# untitled.net
KiCad netlist of a schematic drawn in EAGLE
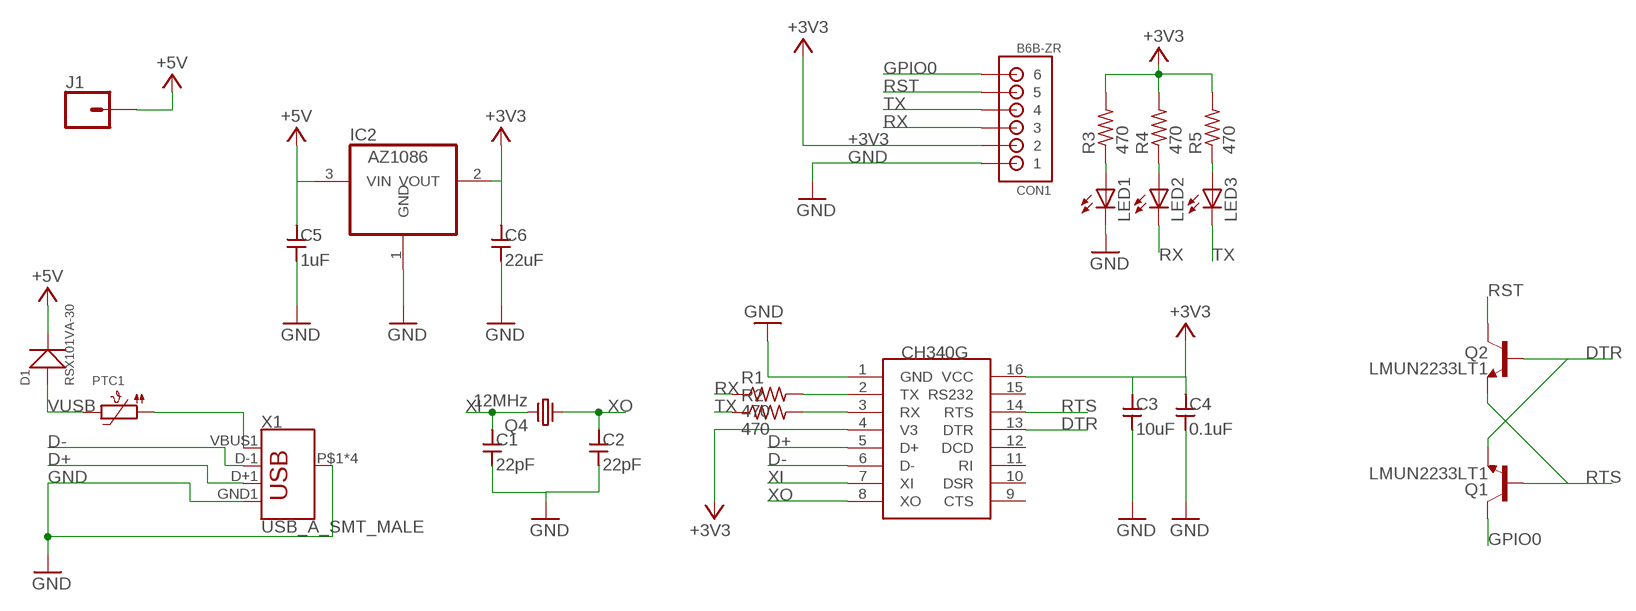
[diagram p0: schematic, sheet 1]

(export (version "E")
  (design (tool "Eeschema 10.0.6"))
  (components
    (comp (ref "C1")
      (value "22pF")
      (footprint "eagle-import:SMD1608")
      (libsource (lib "eagle-import") (part "CAPACITOR1608"))
    )
    (comp (ref "C2")
      (value "22pF")
      (footprint "eagle-import:SMD1608")
      (libsource (lib "eagle-import") (part "CAPACITOR1608"))
    )
    (comp (ref "C3")
      (value "10uF")
      (footprint "eagle-import:SMD1608")
      (libsource (lib "eagle-import") (part "CAPACITOR1608"))
    )
    (comp (ref "C4")
      (value "0.1uF")
      (footprint "eagle-import:SMD1608")
      (libsource (lib "eagle-import") (part "CAPACITOR1608"))
    )
    (comp (ref "C5")
      (value "1uF")
      (footprint "eagle-import:SMD1608")
      (libsource (lib "eagle-import") (part "CAPACITOR1608"))
    )
    (comp (ref "C6")
      (value "22uF")
      (footprint "eagle-import:SMD1608")
      (libsource (lib "eagle-import") (part "CAPACITOR1608"))
    )
    (comp (ref "CON1")
      (value "B6B-ZR")
      (footprint "eagle-import:B6B-ZR")
      (libsource (lib "eagle-import") (part "B6B-ZR"))
    )
    (comp (ref "D1")
      (value "RSX101VA-30")
      (footprint "eagle-import:TUMD2")
      (libsource (lib "eagle-import") (part "DIODETUMD2"))
    )
    (comp (ref "IC2")
      (value "AZ1086")
      (footprint "eagle-import:SOT223")
      (libsource (lib "eagle-import") (part "AZ1086"))
    )
    (comp (ref "J1")
      (value "CONN_01PTH_NO_SILK_YES_STOP")
      (footprint "eagle-import:1X01_NO_SILK")
      (libsource (lib "eagle-import") (part "CONN_01PTH_NO_SILK_YES_STOP"))
    )
    (comp (ref "LED1")
      (value "LEDCHIPLED_0603")
      (footprint "eagle-import:CHIPLED_0603")
      (libsource (lib "eagle-import") (part "LEDCHIPLED_0603"))
    )
    (comp (ref "LED2")
      (value "LEDCHIPLED_0603")
      (footprint "eagle-import:CHIPLED_0603")
      (libsource (lib "eagle-import") (part "LEDCHIPLED_0603"))
    )
    (comp (ref "LED3")
      (value "LEDCHIPLED_0603")
      (footprint "eagle-import:CHIPLED_0603")
      (libsource (lib "eagle-import") (part "LEDCHIPLED_0603"))
    )
    (comp (ref "PTC1")
      (value "PTC0805")
      (footprint "eagle-import:0805")
      (libsource (lib "eagle-import") (part "PTC0805"))
    )
    (comp (ref "Q1")
      (value "LMUN2233LT1")
      (footprint "eagle-import:SOT23-3")
      (libsource (lib "eagle-import") (part "LMUN2233LT1"))
    )
    (comp (ref "Q2")
      (value "LMUN2233LT1")
      (footprint "eagle-import:SOT23-3")
      (libsource (lib "eagle-import") (part "LMUN2233LT1"))
    )
    (comp (ref "Q4")
      (value "12MHz")
      (footprint "eagle-import:TC26H")
      (libsource (lib "eagle-import") (part "CRYSTAL-TC26H"))
    )
    (comp (ref "R1")
      (value "470")
      (footprint "eagle-import:R0603")
      (libsource (lib "eagle-import") (part "R-US_R0603"))
    )
    (comp (ref "R2")
      (value "470")
      (footprint "eagle-import:R0603")
      (libsource (lib "eagle-import") (part "R-US_R0603"))
    )
    (comp (ref "R3")
      (value "470")
      (footprint "eagle-import:R0603")
      (libsource (lib "eagle-import") (part "R-US_R0603"))
    )
    (comp (ref "R4")
      (value "470")
      (footprint "eagle-import:R0603")
      (libsource (lib "eagle-import") (part "R-US_R0603"))
    )
    (comp (ref "R5")
      (value "470")
      (footprint "eagle-import:R0603")
      (libsource (lib "eagle-import") (part "R-US_R0603"))
    )
    (comp (ref "U$1")
      (value "CH340G")
      (footprint "eagle-import:SOIC16")
      (libsource (lib "eagle-import") (part "CH340G"))
    )
    (comp (ref "X1")
      (value "USB_A_SMT_MALE")
      (footprint "eagle-import:USB-A-SMT-MALE")
      (libsource (lib "eagle-import") (part "USB_A_SMT_MALE"))
    )
  )
  (nets
    (net (code "1") (name "+3V3") (class "Default")
      (node (ref "C3") (pin "1") (pinfunction "1_1") (pintype "passive"))
      (node (ref "C4") (pin "1") (pinfunction "1_1") (pintype "passive"))
      (node (ref "C6") (pin "1") (pinfunction "1_1") (pintype "passive"))
      (node (ref "CON1") (pin "2") (pinfunction "2_2") (pintype "bidirectional"))
      (node (ref "IC2") (pin "2") (pinfunction "VOUT_2") (pintype "output"))
      (node (ref "R3") (pin "2") (pinfunction "2_2") (pintype "passive"))
      (node (ref "R4") (pin "2") (pinfunction "2_2") (pintype "passive"))
      (node (ref "R5") (pin "2") (pinfunction "2_2") (pintype "passive"))
      (node (ref "U$1") (pin "16") (pinfunction "VCC_16") (pintype "bidirectional"))
      (node (ref "U$1") (pin "4") (pinfunction "V3_4") (pintype "bidirectional"))
    )
    (net (code "2") (name "+5V") (class "Default")
      (node (ref "C5") (pin "1") (pinfunction "1_1") (pintype "passive"))
      (node (ref "D1") (pin "-") (pinfunction "-_-") (pintype "passive"))
      (node (ref "IC2") (pin "3") (pinfunction "VIN_3") (pintype "input"))
      (node (ref "J1") (pin "1") (pinfunction "1_1") (pintype "passive"))
    )
    (net (code "3") (name "/D+") (class "Default")
      (node (ref "U$1") (pin "5") (pinfunction "D+_5") (pintype "bidirectional"))
      (node (ref "X1") (pin "D+1") (pinfunction "D+_D+1") (pintype "bidirectional"))
    )
    (net (code "4") (name "/D-") (class "Default")
      (node (ref "U$1") (pin "6") (pinfunction "D-_6") (pintype "bidirectional"))
      (node (ref "X1") (pin "D-1") (pinfunction "D-_D-1") (pintype "bidirectional"))
    )
    (net (code "5") (name "/DTR") (class "Default")
      (node (ref "Q1") (pin "3") (pinfunction "E_3") (pintype "passive"))
      (node (ref "Q2") (pin "1") (pinfunction "B_1") (pintype "passive"))
      (node (ref "U$1") (pin "13") (pinfunction "DTR_13") (pintype "bidirectional"))
    )
    (net (code "6") (name "/GPIO0") (class "Default")
      (node (ref "CON1") (pin "6") (pinfunction "6_6") (pintype "bidirectional"))
      (node (ref "Q1") (pin "2") (pinfunction "C_2") (pintype "passive"))
    )
    (net (code "7") (name "/RST") (class "Default")
      (node (ref "CON1") (pin "5") (pinfunction "5_5") (pintype "bidirectional"))
      (node (ref "Q2") (pin "2") (pinfunction "C_2") (pintype "passive"))
    )
    (net (code "8") (name "/RTS") (class "Default")
      (node (ref "Q1") (pin "1") (pinfunction "B_1") (pintype "passive"))
      (node (ref "Q2") (pin "3") (pinfunction "E_3") (pintype "passive"))
      (node (ref "U$1") (pin "14") (pinfunction "RTS_14") (pintype "bidirectional"))
    )
    (net (code "9") (name "/RX") (class "Default")
      (node (ref "CON1") (pin "3") (pinfunction "3_3") (pintype "bidirectional"))
      (node (ref "LED2") (pin "C") (pinfunction "C_C") (pintype "passive"))
      (node (ref "R1") (pin "1") (pinfunction "1_1") (pintype "passive"))
    )
    (net (code "10") (name "/TX") (class "Default")
      (node (ref "CON1") (pin "4") (pinfunction "4_4") (pintype "bidirectional"))
      (node (ref "LED3") (pin "C") (pinfunction "C_C") (pintype "passive"))
      (node (ref "R2") (pin "1") (pinfunction "1_1") (pintype "passive"))
    )
    (net (code "11") (name "/VUSB") (class "Default")
      (node (ref "D1") (pin "+") (pinfunction "+_+") (pintype "passive"))
      (node (ref "PTC1") (pin "2") (pinfunction "2_2") (pintype "passive"))
    )
    (net (code "12") (name "/XI") (class "Default")
      (node (ref "C1") (pin "1") (pinfunction "1_1") (pintype "passive"))
      (node (ref "Q4") (pin "2") (pinfunction "2_2") (pintype "passive"))
      (node (ref "U$1") (pin "7") (pinfunction "XI_7") (pintype "bidirectional"))
    )
    (net (code "13") (name "/XO") (class "Default")
      (node (ref "C2") (pin "1") (pinfunction "1_1") (pintype "passive"))
      (node (ref "Q4") (pin "1") (pinfunction "1_1") (pintype "passive"))
      (node (ref "U$1") (pin "8") (pinfunction "XO_8") (pintype "bidirectional"))
    )
    (net (code "14") (name "GND") (class "Default")
      (node (ref "C1") (pin "2") (pinfunction "2_2") (pintype "passive"))
      (node (ref "C2") (pin "2") (pinfunction "2_2") (pintype "passive"))
      (node (ref "C3") (pin "2") (pinfunction "2_2") (pintype "passive"))
      (node (ref "C4") (pin "2") (pinfunction "2_2") (pintype "passive"))
      (node (ref "C5") (pin "2") (pinfunction "2_2") (pintype "passive"))
      (node (ref "C6") (pin "2") (pinfunction "2_2") (pintype "passive"))
      (node (ref "CON1") (pin "1") (pinfunction "1_1") (pintype "bidirectional"))
      (node (ref "IC2") (pin "1") (pinfunction "GND_1") (pintype "power_in"))
      (node (ref "LED1") (pin "C") (pinfunction "C_C") (pintype "passive"))
      (node (ref "U$1") (pin "1") (pinfunction "GND_1") (pintype "bidirectional"))
      (node (ref "X1") (pin "GND1") (pinfunction "GND_GND1") (pintype "power_in"))
      (node (ref "X1") (pin "P$1") (pinfunction "SHIELD_P$1") (pintype "bidirectional"))
      (node (ref "X1") (pin "P$2") (pinfunction "SHIELD_P$2") (pintype "bidirectional"))
      (node (ref "X1") (pin "P$3") (pinfunction "SHIELD_P$3") (pintype "bidirectional"))
      (node (ref "X1") (pin "P$4") (pinfunction "SHIELD_P$4") (pintype "bidirectional"))
    )
    (net (code "15") (name "Net-(LED1-PadA)") (class "Default")
      (node (ref "LED1") (pin "A") (pinfunction "A_A") (pintype "passive"))
      (node (ref "R3") (pin "1") (pinfunction "1_1") (pintype "passive"))
    )
    (net (code "16") (name "Net-(LED2-PadA)") (class "Default")
      (node (ref "LED2") (pin "A") (pinfunction "A_A") (pintype "passive"))
      (node (ref "R4") (pin "1") (pinfunction "1_1") (pintype "passive"))
    )
    (net (code "17") (name "Net-(LED3-PadA)") (class "Default")
      (node (ref "LED3") (pin "A") (pinfunction "A_A") (pintype "passive"))
      (node (ref "R5") (pin "1") (pinfunction "1_1") (pintype "passive"))
    )
    (net (code "18") (name "Net-(U$1-RX)") (class "Default")
      (node (ref "R2") (pin "2") (pinfunction "2_2") (pintype "passive"))
      (node (ref "U$1") (pin "3") (pinfunction "RX_3") (pintype "bidirectional"))
    )
    (net (code "19") (name "Net-(U$1-TX)") (class "Default")
      (node (ref "R1") (pin "2") (pinfunction "2_2") (pintype "passive"))
      (node (ref "U$1") (pin "2") (pinfunction "TX_2") (pintype "bidirectional"))
    )
    (net (code "20") (name "Net-(X1-VBUS)") (class "Default")
      (node (ref "PTC1") (pin "1") (pinfunction "1_1") (pintype "passive"))
      (node (ref "X1") (pin "VBUS1") (pinfunction "VBUS_VBUS1") (pintype "power_in"))
    )
    (net (code "21") (name "unconnected-(U$1-CTS-Pad9)") (class "Default")
      (node (ref "U$1") (pin "9") (pinfunction "CTS_9") (pintype "bidirectional"))
    )
    (net (code "22") (name "unconnected-(U$1-DCD-Pad12)") (class "Default")
      (node (ref "U$1") (pin "12") (pinfunction "DCD_12") (pintype "bidirectional"))
    )
    (net (code "23") (name "unconnected-(U$1-DSR-Pad10)") (class "Default")
      (node (ref "U$1") (pin "10") (pinfunction "DSR_10") (pintype "bidirectional"))
    )
    (net (code "24") (name "unconnected-(U$1-RI-Pad11)") (class "Default")
      (node (ref "U$1") (pin "11") (pinfunction "RI_11") (pintype "bidirectional"))
    )
    (net (code "25") (name "unconnected-(U$1-RS232-Pad15)") (class "Default")
      (node (ref "U$1") (pin "15") (pinfunction "RS232_15") (pintype "bidirectional"))
    )
  )
)
